# MSP-EXP430F5529LP_3.net
KiCad netlist of a schematic drawn in Altium Designer
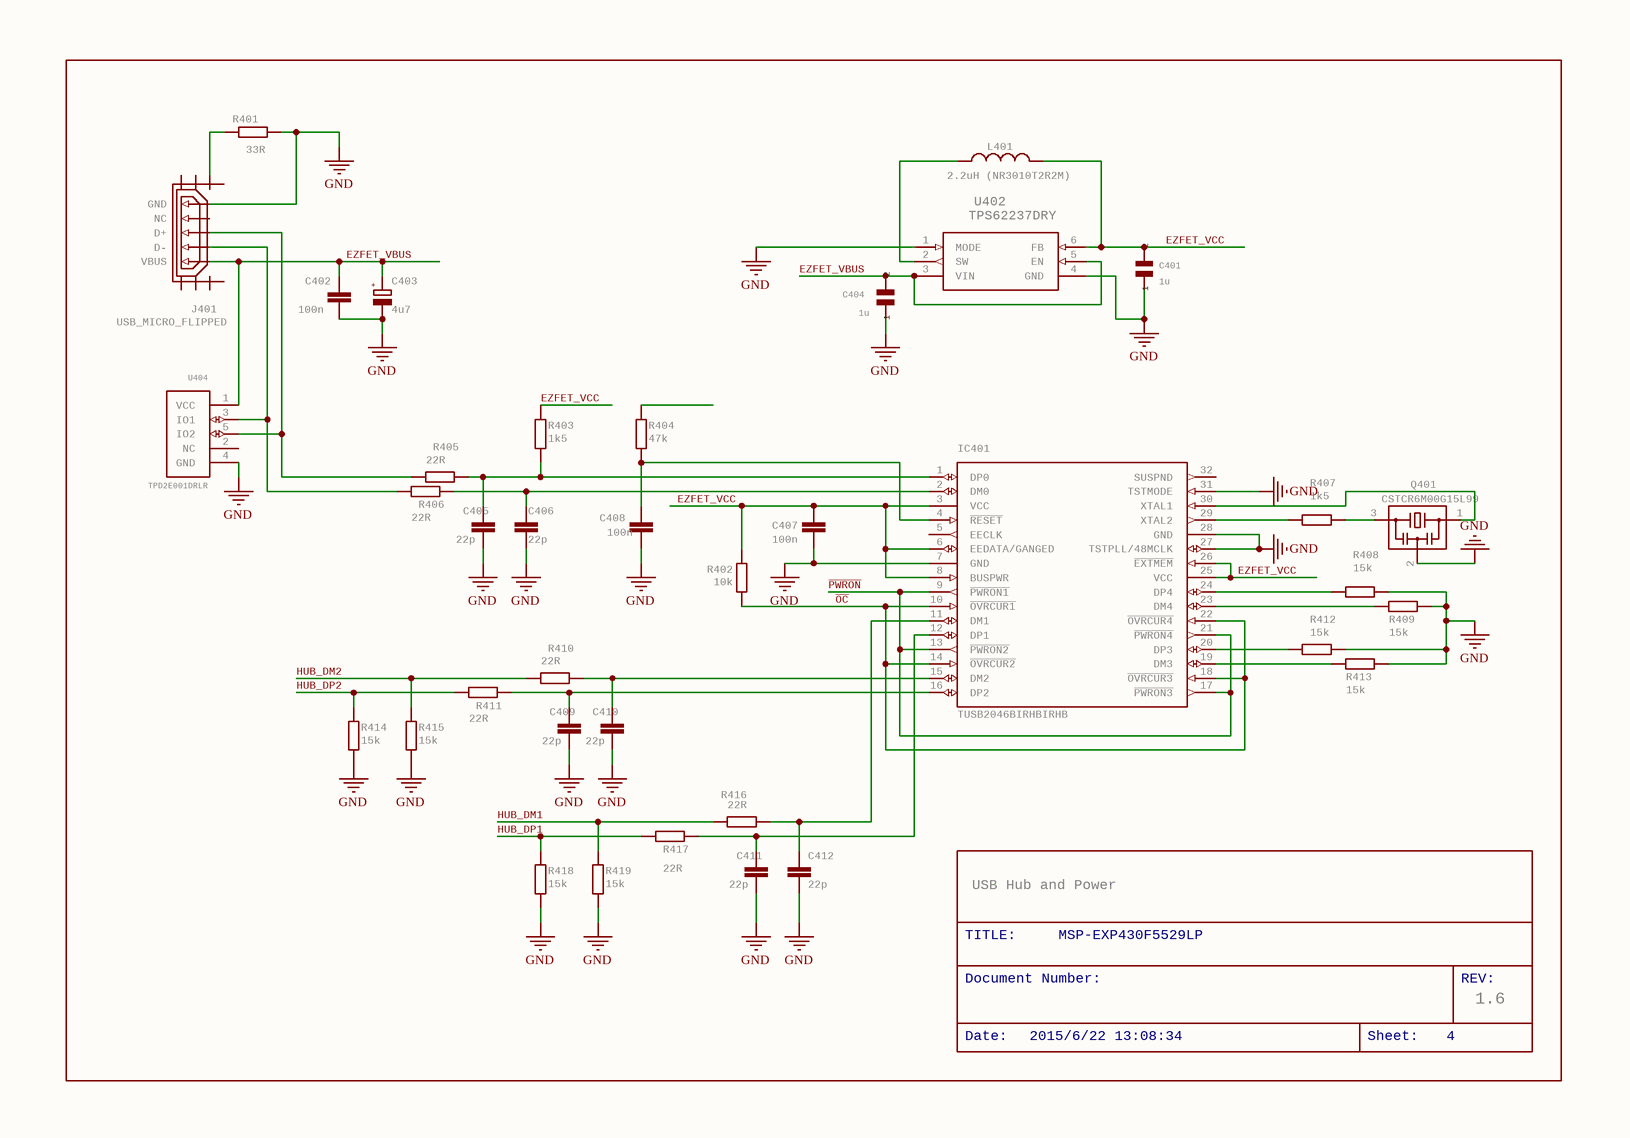
[diagram p0: MSP-EXP430F5529LP_3.SchDoc]

(export (version "E")
  (design (tool "Eeschema 10.0.6"))
  (components
    (comp (ref "C401")
      (value "1u")
      (footprint "CSMD0805")
      (fields (field (name "1") "1") (field (name "2") "2"))
      (libsource (lib "CAP") (part "CSMD0805"))
    )
    (comp (ref "C402")
      (value "100n")
      (footprint "0402")
      (description "CAPACITOR, European symbol")
      (libsource (lib "rcl") (part "C-EUCM0402"))
    )
    (comp (ref "C403")
      (value "4u7")
      (footprint "A/3216-18R")
      (description "POLARIZED CAPACITOR, European symbol")
      (fields (field (name "+") "+"))
      (libsource (lib "rcl") (part "CPOL-EUA/3216-18R"))
    )
    (comp (ref "C404")
      (value "1u")
      (footprint "CSMD0805")
      (fields (field (name "1") "1") (field (name "2") "2"))
      (libsource (lib "CAP") (part "CSMD0805"))
    )
    (comp (ref "C405")
      (value "22p")
      (footprint "0402")
      (description "CAPACITOR, European symbol")
      (libsource (lib "rcl") (part "C-EUCM0402"))
    )
    (comp (ref "C406")
      (value "22p")
      (footprint "0402")
      (description "CAPACITOR, European symbol")
      (libsource (lib "rcl") (part "C-EUCM0402"))
    )
    (comp (ref "C407")
      (value "100n")
      (footprint "0402")
      (description "CAPACITOR, European symbol")
      (libsource (lib "rcl") (part "C-EUCM0402"))
    )
    (comp (ref "C408")
      (value "100n")
      (footprint "0402")
      (description "CAPACITOR, European symbol")
      (libsource (lib "rcl") (part "C-EUCM0402"))
    )
    (comp (ref "C409")
      (value "22p")
      (footprint "0402")
      (description "CAPACITOR, European symbol")
      (libsource (lib "rcl") (part "C-EUCM0402"))
    )
    (comp (ref "C410")
      (value "22p")
      (footprint "0402")
      (description "CAPACITOR, European symbol")
      (libsource (lib "rcl") (part "C-EUCM0402"))
    )
    (comp (ref "C411")
      (value "22p")
      (footprint "0402")
      (description "CAPACITOR, European symbol")
      (libsource (lib "rcl") (part "C-EUCM0402"))
    )
    (comp (ref "C412")
      (value "22p")
      (footprint "0402")
      (description "CAPACITOR, European symbol")
      (libsource (lib "rcl") (part "C-EUCM0402"))
    )
    (comp (ref "IC401")
      (value "TUSB2046BIRHBIRHB")
      (footprint "RHB_S-PQFP-N32")
      (fields (field (name "MF") "MF") (field (name "MPN") "TUSB2046BIRHBT"))
      (libsource (lib "texas") (part "TUSB2046BIRHBIRHB"))
    )
    (comp (ref "J401")
      (value "USB_MICRO_FLIPPED")
      (footprint "HIROSE-ZX62R-B-5P")
      (libsource (lib "usb_con-update") (part "USB_MICRO_FLIPPED"))
    )
    (comp (ref "L401")
      (value "2.2uH (NR3010T2R2M)")
      (footprint "L-NR3010")
      (libsource (lib "MSP-EXP430F5659") (part "L-NR3010"))
    )
    (comp (ref "Q401")
      (value "CSTCR6M00G15L99")
      (footprint "MURATA-FILTER_CSTCR")
      (description "Resonator   Source: murata.co.jp")
      (fields (field (name "MF") "MF") (field (name "MPN") "CSTCR6M00G53-R0"))
      (libsource (lib "murata") (part "MURATA-FILTER_CSTCR"))
    )
    (comp (ref "R401")
      (value "33R")
      (footprint "0402")
      (description "RESISTOR, European symbol")
      (libsource (lib "rcl") (part "R-EU_RM0402"))
    )
    (comp (ref "R402")
      (value "10k")
      (footprint "0402")
      (description "RESISTOR, European symbol")
      (libsource (lib "rcl") (part "R-EU_RM0402"))
    )
    (comp (ref "R403")
      (value "1k5")
      (footprint "0402")
      (description "RESISTOR, European symbol")
      (libsource (lib "rcl") (part "R-EU_RM0402"))
    )
    (comp (ref "R404")
      (value "47k")
      (footprint "0402")
      (description "RESISTOR, European symbol")
      (libsource (lib "rcl") (part "R-EU_RM0402"))
    )
    (comp (ref "R405")
      (value "22R")
      (footprint "0402")
      (description "RESISTOR, European symbol")
      (libsource (lib "rcl") (part "R-EU_RM0402"))
    )
    (comp (ref "R406")
      (value "22R")
      (footprint "0402")
      (description "RESISTOR, European symbol")
      (libsource (lib "rcl") (part "R-EU_RM0402"))
    )
    (comp (ref "R407")
      (value "1k5")
      (footprint "0402")
      (description "RESISTOR, European symbol")
      (libsource (lib "rcl") (part "R-EU_RM0402"))
    )
    (comp (ref "R408")
      (value "15k")
      (footprint "0402")
      (description "RESISTOR, European symbol")
      (libsource (lib "rcl") (part "R-EU_RM0402"))
    )
    (comp (ref "R409")
      (value "15k")
      (footprint "0402")
      (description "RESISTOR, European symbol")
      (libsource (lib "rcl") (part "R-EU_RM0402"))
    )
    (comp (ref "R410")
      (value "22R")
      (footprint "0402")
      (description "RESISTOR, European symbol")
      (libsource (lib "rcl") (part "R-EU_RM0402"))
    )
    (comp (ref "R411")
      (value "22R")
      (footprint "0402")
      (description "RESISTOR, European symbol")
      (libsource (lib "rcl") (part "R-EU_RM0402"))
    )
    (comp (ref "R412")
      (value "15k")
      (footprint "0402")
      (description "RESISTOR, European symbol")
      (libsource (lib "rcl") (part "R-EU_RM0402"))
    )
    (comp (ref "R413")
      (value "15k")
      (footprint "0402")
      (description "RESISTOR, European symbol")
      (libsource (lib "rcl") (part "R-EU_RM0402"))
    )
    (comp (ref "R414")
      (value "15k")
      (footprint "0402")
      (description "RESISTOR, European symbol")
      (libsource (lib "rcl") (part "R-EU_RM0402"))
    )
    (comp (ref "R415")
      (value "15k")
      (footprint "0402")
      (description "RESISTOR, European symbol")
      (libsource (lib "rcl") (part "R-EU_RM0402"))
    )
    (comp (ref "R416")
      (value "22R")
      (footprint "0402")
      (description "RESISTOR, European symbol")
      (libsource (lib "rcl") (part "R-EU_RM0402"))
    )
    (comp (ref "R417")
      (value "22R")
      (footprint "0402")
      (description "RESISTOR, European symbol")
      (libsource (lib "rcl") (part "R-EU_RM0402"))
    )
    (comp (ref "R418")
      (value "15k")
      (footprint "0402")
      (description "RESISTOR, European symbol")
      (libsource (lib "rcl") (part "R-EU_RM0402"))
    )
    (comp (ref "R419")
      (value "15k")
      (footprint "0402")
      (description "RESISTOR, European symbol")
      (libsource (lib "rcl") (part "R-EU_RM0402"))
    )
    (comp (ref "U402")
      (value "TPS62237DRY")
      (footprint "DRY6")
      (description "3 MHz Ultra Small Step Down Converter in 1x1.5 SON Package")
      (fields
        (field (name "GENERIC_PART_NUMBER") "TPS62231")
        (field (name "MANUFACTURER") "Texas Instruments")
      )
      (libsource (lib "tps62231dry") (part "TPS6223X_DRY_6"))
    )
    (comp (ref "U404")
      (value "TPD2E001DRLR")
      (footprint "TPD2E001-DRL")
      (description "TPD2E001 ESD-protection diode array")
      (libsource (lib "Project7264") (part "TPD2E001"))
    )
  )
  (nets
    (net (code "1") (name "/EZFET_VBUS") (class "Default")
      (node (ref "C402") (pin "1") (pinfunction "1_1") (pintype "passive"))
      (node (ref "C403") (pin "+") (pinfunction "+_+") (pintype "passive"))
      (node (ref "C404") (pin "2") (pinfunction "2_2") (pintype "passive"))
      (node (ref "J401") (pin "VBUS") (pinfunction "VBUS_VBUS") (pintype "input"))
      (node (ref "U402") (pin "3") (pinfunction "VIN_3") (pintype "power_in"))
      (node (ref "U402") (pin "5") (pinfunction "EN_5") (pintype "input"))
      (node (ref "U404") (pin "1") (pinfunction "VCC_1") (pintype "power_in"))
    )
    (net (code "2") (name "/EZFET_VCC") (class "Default")
      (node (ref "C401") (pin "2") (pinfunction "2_2") (pintype "passive"))
      (node (ref "C407") (pin "1") (pinfunction "1_1") (pintype "passive"))
      (node (ref "IC401") (pin "25") (pinfunction "VCC_25") (pintype "power_in"))
      (node (ref "IC401") (pin "26") (pinfunction "~{EXTMEM}_26") (pintype "input"))
      (node (ref "IC401") (pin "3") (pinfunction "VCC_3") (pintype "power_in"))
      (node (ref "IC401") (pin "6") (pinfunction "EEDATA/GANGED_6") (pintype "bidirectional"))
      (node (ref "IC401") (pin "8") (pinfunction "BUSPWR_8") (pintype "input"))
      (node (ref "L401") (pin "P$2") (pinfunction "2_P$2") (pintype "passive"))
      (node (ref "R402") (pin "1") (pinfunction "1_1") (pintype "passive"))
      (node (ref "R403") (pin "1") (pinfunction "1_1") (pintype "passive"))
      (node (ref "U402") (pin "6") (pinfunction "FB_6") (pintype "input"))
    )
    (net (code "3") (name "/HUB_DM1") (class "Default")
      (node (ref "R416") (pin "2") (pinfunction "2_2") (pintype "passive"))
      (node (ref "R419") (pin "1") (pinfunction "1_1") (pintype "passive"))
    )
    (net (code "4") (name "/HUB_DM2") (class "Default")
      (node (ref "R410") (pin "2") (pinfunction "2_2") (pintype "passive"))
      (node (ref "R415") (pin "1") (pinfunction "1_1") (pintype "passive"))
    )
    (net (code "5") (name "/HUB_DP1") (class "Default")
      (node (ref "R417") (pin "2") (pinfunction "2_2") (pintype "passive"))
      (node (ref "R418") (pin "1") (pinfunction "1_1") (pintype "passive"))
    )
    (net (code "6") (name "/HUB_DP2") (class "Default")
      (node (ref "R411") (pin "2") (pinfunction "2_2") (pintype "passive"))
      (node (ref "R414") (pin "1") (pinfunction "1_1") (pintype "passive"))
    )
    (net (code "7") (name "/~{OC}") (class "Default")
      (node (ref "IC401") (pin "10") (pinfunction "~{OVRCUR1}_10") (pintype "input"))
      (node (ref "IC401") (pin "14") (pinfunction "~{OVRCUR2}_14") (pintype "input"))
      (node (ref "IC401") (pin "18") (pinfunction "~{OVRCUR3}_18") (pintype "input"))
      (node (ref "IC401") (pin "22") (pinfunction "~{OVRCUR4}_22") (pintype "input"))
      (node (ref "R402") (pin "2") (pinfunction "2_2") (pintype "passive"))
    )
    (net (code "8") (name "/~{PWRON}") (class "Default")
      (node (ref "IC401") (pin "13") (pinfunction "~{PWRON2}_13") (pintype "output"))
      (node (ref "IC401") (pin "17") (pinfunction "~{PWRON3}_17") (pintype "output"))
      (node (ref "IC401") (pin "21") (pinfunction "~{PWRON4}_21") (pintype "output"))
      (node (ref "IC401") (pin "9") (pinfunction "~{PWRON1}_9") (pintype "output"))
    )
    (net (code "9") (name "GND") (class "Default")
      (node (ref "C401") (pin "1") (pinfunction "1_1") (pintype "passive"))
      (node (ref "C402") (pin "2") (pinfunction "2_2") (pintype "passive"))
      (node (ref "C403") (pin "-") (pinfunction "-_-") (pintype "passive"))
      (node (ref "C404") (pin "1") (pinfunction "1_1") (pintype "passive"))
      (node (ref "C405") (pin "2") (pinfunction "2_2") (pintype "passive"))
      (node (ref "C406") (pin "2") (pinfunction "2_2") (pintype "passive"))
      (node (ref "C407") (pin "2") (pinfunction "2_2") (pintype "passive"))
      (node (ref "C408") (pin "2") (pinfunction "2_2") (pintype "passive"))
      (node (ref "C409") (pin "2") (pinfunction "2_2") (pintype "passive"))
      (node (ref "C410") (pin "2") (pinfunction "2_2") (pintype "passive"))
      (node (ref "C411") (pin "2") (pinfunction "2_2") (pintype "passive"))
      (node (ref "C412") (pin "2") (pinfunction "2_2") (pintype "passive"))
      (node (ref "IC401") (pin "27") (pinfunction "TSTPLL/48MCLK_27") (pintype "bidirectional"))
      (node (ref "IC401") (pin "28") (pinfunction "GND_28") (pintype "power_in"))
      (node (ref "IC401") (pin "31") (pinfunction "TSTMODE_31") (pintype "input"))
      (node (ref "IC401") (pin "7") (pinfunction "GND_7") (pintype "power_in"))
      (node (ref "J401") (pin "GND") (pinfunction "GND_GND") (pintype "input"))
      (node (ref "Q401") (pin "2") (pinfunction "2_2") (pintype "passive"))
      (node (ref "R401") (pin "2") (pinfunction "2_2") (pintype "passive"))
      (node (ref "R408") (pin "1") (pinfunction "1_1") (pintype "passive"))
      (node (ref "R409") (pin "1") (pinfunction "1_1") (pintype "passive"))
      (node (ref "R412") (pin "1") (pinfunction "1_1") (pintype "passive"))
      (node (ref "R413") (pin "1") (pinfunction "1_1") (pintype "passive"))
      (node (ref "R414") (pin "2") (pinfunction "2_2") (pintype "passive"))
      (node (ref "R415") (pin "2") (pinfunction "2_2") (pintype "passive"))
      (node (ref "R418") (pin "2") (pinfunction "2_2") (pintype "passive"))
      (node (ref "R419") (pin "2") (pinfunction "2_2") (pintype "passive"))
      (node (ref "U402") (pin "1") (pinfunction "MODE_1") (pintype "input"))
      (node (ref "U402") (pin "4") (pinfunction "GND_4") (pintype "power_in"))
      (node (ref "U404") (pin "4") (pinfunction "GND_4") (pintype "power_in"))
    )
    (net (code "10") (name "Net-(IC401-DM0)") (class "Default")
      (node (ref "C406") (pin "1") (pinfunction "1_1") (pintype "passive"))
      (node (ref "IC401") (pin "2") (pinfunction "DM0_2") (pintype "bidirectional"))
      (node (ref "R406") (pin "1") (pinfunction "1_1") (pintype "passive"))
    )
    (net (code "11") (name "Net-(IC401-DM1)") (class "Default")
      (node (ref "C412") (pin "1") (pinfunction "1_1") (pintype "passive"))
      (node (ref "IC401") (pin "11") (pinfunction "DM1_11") (pintype "bidirectional"))
      (node (ref "R416") (pin "1") (pinfunction "1_1") (pintype "passive"))
    )
    (net (code "12") (name "Net-(IC401-DM2)") (class "Default")
      (node (ref "C410") (pin "1") (pinfunction "1_1") (pintype "passive"))
      (node (ref "IC401") (pin "15") (pinfunction "DM2_15") (pintype "bidirectional"))
      (node (ref "R410") (pin "1") (pinfunction "1_1") (pintype "passive"))
    )
    (net (code "13") (name "Net-(IC401-DM3)") (class "Default")
      (node (ref "IC401") (pin "19") (pinfunction "DM3_19") (pintype "bidirectional"))
      (node (ref "R413") (pin "2") (pinfunction "2_2") (pintype "passive"))
    )
    (net (code "14") (name "Net-(IC401-DM4)") (class "Default")
      (node (ref "IC401") (pin "23") (pinfunction "DM4_23") (pintype "bidirectional"))
      (node (ref "R409") (pin "2") (pinfunction "2_2") (pintype "passive"))
    )
    (net (code "15") (name "Net-(IC401-DP0)") (class "Default")
      (node (ref "C405") (pin "1") (pinfunction "1_1") (pintype "passive"))
      (node (ref "IC401") (pin "1") (pinfunction "DP0_1") (pintype "bidirectional"))
      (node (ref "R403") (pin "2") (pinfunction "2_2") (pintype "passive"))
      (node (ref "R405") (pin "1") (pinfunction "1_1") (pintype "passive"))
    )
    (net (code "16") (name "Net-(IC401-DP1)") (class "Default")
      (node (ref "C411") (pin "1") (pinfunction "1_1") (pintype "passive"))
      (node (ref "IC401") (pin "12") (pinfunction "DP1_12") (pintype "bidirectional"))
      (node (ref "R417") (pin "1") (pinfunction "1_1") (pintype "passive"))
    )
    (net (code "17") (name "Net-(IC401-DP2)") (class "Default")
      (node (ref "C409") (pin "1") (pinfunction "1_1") (pintype "passive"))
      (node (ref "IC401") (pin "16") (pinfunction "DP2_16") (pintype "bidirectional"))
      (node (ref "R411") (pin "1") (pinfunction "1_1") (pintype "passive"))
    )
    (net (code "18") (name "Net-(IC401-DP3)") (class "Default")
      (node (ref "IC401") (pin "20") (pinfunction "DP3_20") (pintype "bidirectional"))
      (node (ref "R412") (pin "2") (pinfunction "2_2") (pintype "passive"))
    )
    (net (code "19") (name "Net-(IC401-DP4)") (class "Default")
      (node (ref "IC401") (pin "24") (pinfunction "DP4_24") (pintype "bidirectional"))
      (node (ref "R408") (pin "2") (pinfunction "2_2") (pintype "passive"))
    )
    (net (code "20") (name "Net-(IC401-XTAL1)") (class "Default")
      (node (ref "IC401") (pin "30") (pinfunction "XTAL1_30") (pintype "input"))
      (node (ref "Q401") (pin "1") (pinfunction "1_1") (pintype "passive"))
    )
    (net (code "21") (name "Net-(IC401-XTAL2)") (class "Default")
      (node (ref "IC401") (pin "29") (pinfunction "XTAL2_29") (pintype "output"))
      (node (ref "R407") (pin "2") (pinfunction "2_2") (pintype "passive"))
    )
    (net (code "22") (name "Net-(IC401-~{RESET})") (class "Default")
      (node (ref "C408") (pin "1") (pinfunction "1_1") (pintype "passive"))
      (node (ref "IC401") (pin "4") (pinfunction "~{RESET}_4") (pintype "input"))
      (node (ref "R404") (pin "2") (pinfunction "2_2") (pintype "passive"))
    )
    (net (code "23") (name "Net-(J401-PadSHIELD1)") (class "Default")
      (node (ref "J401") (pin "SHIELD1") (pinfunction "SHIELD1_SHIELD1") (pintype "bidirectional"))
      (node (ref "R401") (pin "1") (pinfunction "1_1") (pintype "passive"))
    )
    (net (code "24") (name "Net-(L401-1)") (class "Default")
      (node (ref "L401") (pin "P$1") (pinfunction "1_P$1") (pintype "passive"))
      (node (ref "U402") (pin "2") (pinfunction "SW_2") (pintype "output"))
    )
    (net (code "25") (name "Net-(Q401-Pad3)") (class "Default")
      (node (ref "Q401") (pin "3") (pinfunction "3_3") (pintype "passive"))
      (node (ref "R407") (pin "1") (pinfunction "1_1") (pintype "passive"))
    )
    (net (code "26") (name "Net-(U404-IO1)") (class "Default")
      (node (ref "J401") (pin "D-") (pinfunction "D-_D-") (pintype "input"))
      (node (ref "R406") (pin "2") (pinfunction "2_2") (pintype "passive"))
      (node (ref "U404") (pin "3") (pinfunction "IO1_3") (pintype "bidirectional"))
    )
    (net (code "27") (name "Net-(U404-IO2)") (class "Default")
      (node (ref "J401") (pin "D+") (pinfunction "D+_D+") (pintype "input"))
      (node (ref "R405") (pin "2") (pinfunction "2_2") (pintype "passive"))
      (node (ref "U404") (pin "5") (pinfunction "IO2_5") (pintype "bidirectional"))
    )
    (net (code "28") (name "unconnected-(IC401-EECLK-Pad5)") (class "Default")
      (node (ref "IC401") (pin "5") (pinfunction "EECLK_5") (pintype "output"))
    )
    (net (code "29") (name "unconnected-(IC401-SUSPND-Pad32)") (class "Default")
      (node (ref "IC401") (pin "32") (pinfunction "SUSPND_32") (pintype "output"))
    )
    (net (code "30") (name "unconnected-(J401-PadNC)") (class "Default")
      (node (ref "J401") (pin "NC") (pinfunction "NC_NC") (pintype "input"))
    )
    (net (code "31") (name "unconnected-(J401-PadSHIELD2)") (class "Default")
      (node (ref "J401") (pin "SHIELD2") (pinfunction "SHIELD2_SHIELD2") (pintype "bidirectional"))
    )
    (net (code "32") (name "unconnected-(J401-PadSHIELD3)") (class "Default")
      (node (ref "J401") (pin "SHIELD3") (pinfunction "SHIELD3_SHIELD3") (pintype "bidirectional"))
    )
    (net (code "33") (name "unconnected-(J401-PadSHIELD4)") (class "Default")
      (node (ref "J401") (pin "SHIELD4") (pinfunction "SHIELD4_SHIELD4") (pintype "bidirectional"))
    )
    (net (code "34") (name "unconnected-(J401-PadSHIELD5)") (class "Default")
      (node (ref "J401") (pin "SHIELD5") (pinfunction "SHIELD5_SHIELD5") (pintype "bidirectional"))
    )
    (net (code "35") (name "unconnected-(J401-PadSHIELD6)") (class "Default")
      (node (ref "J401") (pin "SHIELD6") (pinfunction "SHIELD6_SHIELD6") (pintype "bidirectional"))
    )
    (net (code "36") (name "unconnected-(R404-Pad1)") (class "Default")
      (node (ref "R404") (pin "1") (pinfunction "1_1") (pintype "passive"))
    )
    (net (code "37") (name "unconnected-(U404-NC-Pad2)") (class "Default")
      (node (ref "U404") (pin "2") (pinfunction "NC_2") (pintype "passive"))
    )
  )
)
